# EngineLightControl_v1_1.net
KiCad netlist of a schematic drawn in EAGLE
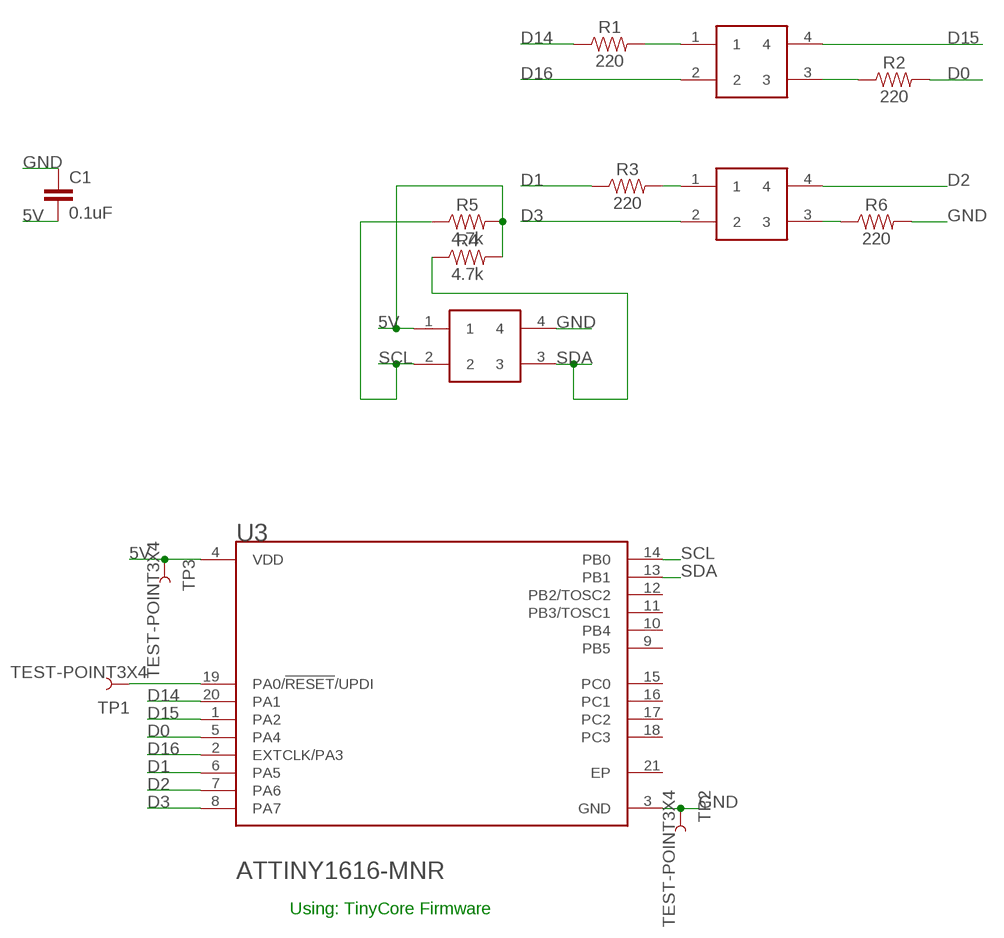
[diagram p0: schematic, sheet 1]

(export (version "E")
  (design (tool "Eeschema 10.0.6"))
  (components
    (comp (ref "C1")
      (value "0.1uF")
      (footprint "eagle-import:0603")
      (libsource (lib "eagle-import") (part "0.1UF-0603-25V-(+80/-20%)"))
    )
    (comp (ref "R1")
      (value "220")
      (footprint "eagle-import:0603")
      (libsource (lib "eagle-import") (part "220OHM-0603-1/10W-1%"))
    )
    (comp (ref "R2")
      (value "220")
      (footprint "eagle-import:0603")
      (libsource (lib "eagle-import") (part "220OHM-0603-1/10W-1%"))
    )
    (comp (ref "R3")
      (value "220")
      (footprint "eagle-import:0603")
      (libsource (lib "eagle-import") (part "220OHM-0603-1/10W-1%"))
    )
    (comp (ref "R4")
      (value "4.7k")
      (footprint "eagle-import:0603")
      (libsource (lib "eagle-import") (part "4.7KOHM-0603-1/10W-1%"))
    )
    (comp (ref "R5")
      (value "4.7k")
      (footprint "eagle-import:0603")
      (libsource (lib "eagle-import") (part "4.7KOHM-0603-1/10W-1%"))
    )
    (comp (ref "R6")
      (value "220")
      (footprint "eagle-import:0603")
      (libsource (lib "eagle-import") (part "220OHM-0603-1/10W-1%"))
    )
    (comp (ref "TP1")
      (value "TEST-POINT3X4")
      (footprint "eagle-import:PAD.03X.04")
      (libsource (lib "eagle-import") (part "TEST-POINT3X4"))
    )
    (comp (ref "TP2")
      (value "TEST-POINT3X4")
      (footprint "eagle-import:PAD.03X.04")
      (libsource (lib "eagle-import") (part "TEST-POINT3X4"))
    )
    (comp (ref "TP3")
      (value "TEST-POINT3X4")
      (footprint "eagle-import:PAD.03X.04")
      (libsource (lib "eagle-import") (part "TEST-POINT3X4"))
    )
    (comp (ref "U$1")
      (value "CONN_M04")
      (footprint "eagle-import:CONN_04")
      (libsource (lib "eagle-import") (part "CONN_M04"))
    )
    (comp (ref "U$2")
      (value "CONN_M04")
      (footprint "eagle-import:CONN_04")
      (libsource (lib "eagle-import") (part "CONN_M04"))
    )
    (comp (ref "U$3")
      (value "CONN_M04")
      (footprint "eagle-import:CONN_04")
      (libsource (lib "eagle-import") (part "CONN_M04"))
    )
    (comp (ref "U3")
      (value "MICROCHIP_ATTINY1616-MNRMICROCHIP_ATTINY1616-MNR_0_0")
      (footprint "eagle-import:MICROCHIP_ATTINY1616-MNR_0")
      (fields
        (field (name "DIGIKEY_PART_NUMBER") "ATTINY1616-MNRCT-ND")
        (field (name "MF") "Microchip")
        (field (name "MOUSER_PART_NUMBER") "556-ATTINY1616MNR")
      )
      (libsource (lib "eagle-import") (part "MICROCHIP_ATTINY1616-MNRMICROCHIP_ATTINY1616-MNR_0_0"))
    )
  )
  (nets
    (net (code "1") (name "/5V") (class "Default")
      (node (ref "C1") (pin "2") (pinfunction "2_2") (pintype "passive"))
      (node (ref "R4") (pin "2") (pinfunction "2_2") (pintype "passive"))
      (node (ref "R5") (pin "2") (pinfunction "2_2") (pintype "passive"))
      (node (ref "TP3") (pin "P$1") (pinfunction "1_P$1") (pintype "bidirectional"))
      (node (ref "U$1") (pin "1") (pinfunction "1_1") (pintype "bidirectional"))
      (node (ref "U3") (pin "4") (pinfunction "VDD_4") (pintype "power_in"))
    )
    (net (code "2") (name "/D0") (class "Default")
      (node (ref "R2") (pin "2") (pinfunction "2_2") (pintype "passive"))
      (node (ref "U3") (pin "5") (pinfunction "PA4_5") (pintype "bidirectional"))
    )
    (net (code "3") (name "/D1") (class "Default")
      (node (ref "R3") (pin "1") (pinfunction "1_1") (pintype "passive"))
      (node (ref "U3") (pin "6") (pinfunction "PA5_6") (pintype "bidirectional"))
    )
    (net (code "4") (name "/D2") (class "Default")
      (node (ref "U$3") (pin "4") (pinfunction "4_4") (pintype "bidirectional"))
      (node (ref "U3") (pin "7") (pinfunction "PA6_7") (pintype "bidirectional"))
    )
    (net (code "5") (name "/D3") (class "Default")
      (node (ref "U$3") (pin "2") (pinfunction "2_2") (pintype "bidirectional"))
      (node (ref "U3") (pin "8") (pinfunction "PA7_8") (pintype "bidirectional"))
    )
    (net (code "6") (name "/D14") (class "Default")
      (node (ref "R1") (pin "1") (pinfunction "1_1") (pintype "passive"))
      (node (ref "U3") (pin "20") (pinfunction "PA1_20") (pintype "bidirectional"))
    )
    (net (code "7") (name "/D15") (class "Default")
      (node (ref "U$2") (pin "4") (pinfunction "4_4") (pintype "bidirectional"))
      (node (ref "U3") (pin "1") (pinfunction "PA2_1") (pintype "bidirectional"))
    )
    (net (code "8") (name "/D16") (class "Default")
      (node (ref "U$2") (pin "2") (pinfunction "2_2") (pintype "bidirectional"))
      (node (ref "U3") (pin "2") (pinfunction "EXTCLK/PA3_2") (pintype "bidirectional"))
    )
    (net (code "9") (name "/EP") (class "Default")
      (node (ref "U3") (pin "21") (pinfunction "EP_21") (pintype "power_in"))
    )
    (net (code "10") (name "/GND") (class "Default")
      (node (ref "C1") (pin "1") (pinfunction "1_1") (pintype "passive"))
      (node (ref "R6") (pin "2") (pinfunction "2_2") (pintype "passive"))
      (node (ref "TP2") (pin "P$1") (pinfunction "1_P$1") (pintype "bidirectional"))
      (node (ref "U$1") (pin "4") (pinfunction "4_4") (pintype "bidirectional"))
      (node (ref "U3") (pin "3") (pinfunction "GND_3") (pintype "power_in"))
    )
    (net (code "11") (name "/SCL") (class "Default")
      (node (ref "R5") (pin "1") (pinfunction "1_1") (pintype "passive"))
      (node (ref "U$1") (pin "2") (pinfunction "2_2") (pintype "bidirectional"))
      (node (ref "U3") (pin "14") (pinfunction "PB0_14") (pintype "bidirectional"))
    )
    (net (code "12") (name "/SDA") (class "Default")
      (node (ref "R4") (pin "1") (pinfunction "1_1") (pintype "passive"))
      (node (ref "U$1") (pin "3") (pinfunction "3_3") (pintype "bidirectional"))
      (node (ref "U3") (pin "13") (pinfunction "PB1_13") (pintype "bidirectional"))
    )
    (net (code "13") (name "Net-(R1-Pad2)") (class "Default")
      (node (ref "R1") (pin "2") (pinfunction "2_2") (pintype "passive"))
      (node (ref "U$2") (pin "1") (pinfunction "1_1") (pintype "bidirectional"))
    )
    (net (code "14") (name "Net-(R2-Pad1)") (class "Default")
      (node (ref "R2") (pin "1") (pinfunction "1_1") (pintype "passive"))
      (node (ref "U$2") (pin "3") (pinfunction "3_3") (pintype "bidirectional"))
    )
    (net (code "15") (name "Net-(R3-Pad2)") (class "Default")
      (node (ref "R3") (pin "2") (pinfunction "2_2") (pintype "passive"))
      (node (ref "U$3") (pin "1") (pinfunction "1_1") (pintype "bidirectional"))
    )
    (net (code "16") (name "Net-(R6-Pad1)") (class "Default")
      (node (ref "R6") (pin "1") (pinfunction "1_1") (pintype "passive"))
      (node (ref "U$3") (pin "3") (pinfunction "3_3") (pintype "bidirectional"))
    )
    (net (code "17") (name "Net-(TP1-1)") (class "Default")
      (node (ref "TP1") (pin "P$1") (pinfunction "1_P$1") (pintype "bidirectional"))
      (node (ref "U3") (pin "19") (pinfunction "PA0/~{RESET}/UPDI_19") (pintype "bidirectional"))
    )
    (net (code "18") (name "unconnected-(U3-PB2{slash}TOSC2-Pad12)") (class "Default")
      (node (ref "U3") (pin "12") (pinfunction "PB2/TOSC2_12") (pintype "bidirectional"))
    )
    (net (code "19") (name "unconnected-(U3-PB3{slash}TOSC1-Pad11)") (class "Default")
      (node (ref "U3") (pin "11") (pinfunction "PB3/TOSC1_11") (pintype "bidirectional"))
    )
    (net (code "20") (name "unconnected-(U3-PB4-Pad10)") (class "Default")
      (node (ref "U3") (pin "10") (pinfunction "PB4_10") (pintype "bidirectional"))
    )
    (net (code "21") (name "unconnected-(U3-PB5-Pad9)") (class "Default")
      (node (ref "U3") (pin "9") (pinfunction "PB5_9") (pintype "bidirectional"))
    )
    (net (code "22") (name "unconnected-(U3-PC0-Pad15)") (class "Default")
      (node (ref "U3") (pin "15") (pinfunction "PC0_15") (pintype "bidirectional"))
    )
    (net (code "23") (name "unconnected-(U3-PC1-Pad16)") (class "Default")
      (node (ref "U3") (pin "16") (pinfunction "PC1_16") (pintype "bidirectional"))
    )
    (net (code "24") (name "unconnected-(U3-PC2-Pad17)") (class "Default")
      (node (ref "U3") (pin "17") (pinfunction "PC2_17") (pintype "bidirectional"))
    )
    (net (code "25") (name "unconnected-(U3-PC3-Pad18)") (class "Default")
      (node (ref "U3") (pin "18") (pinfunction "PC3_18") (pintype "bidirectional"))
    )
  )
)
